# base_pcb_328.net
KiCad netlist of a schematic drawn in EAGLE
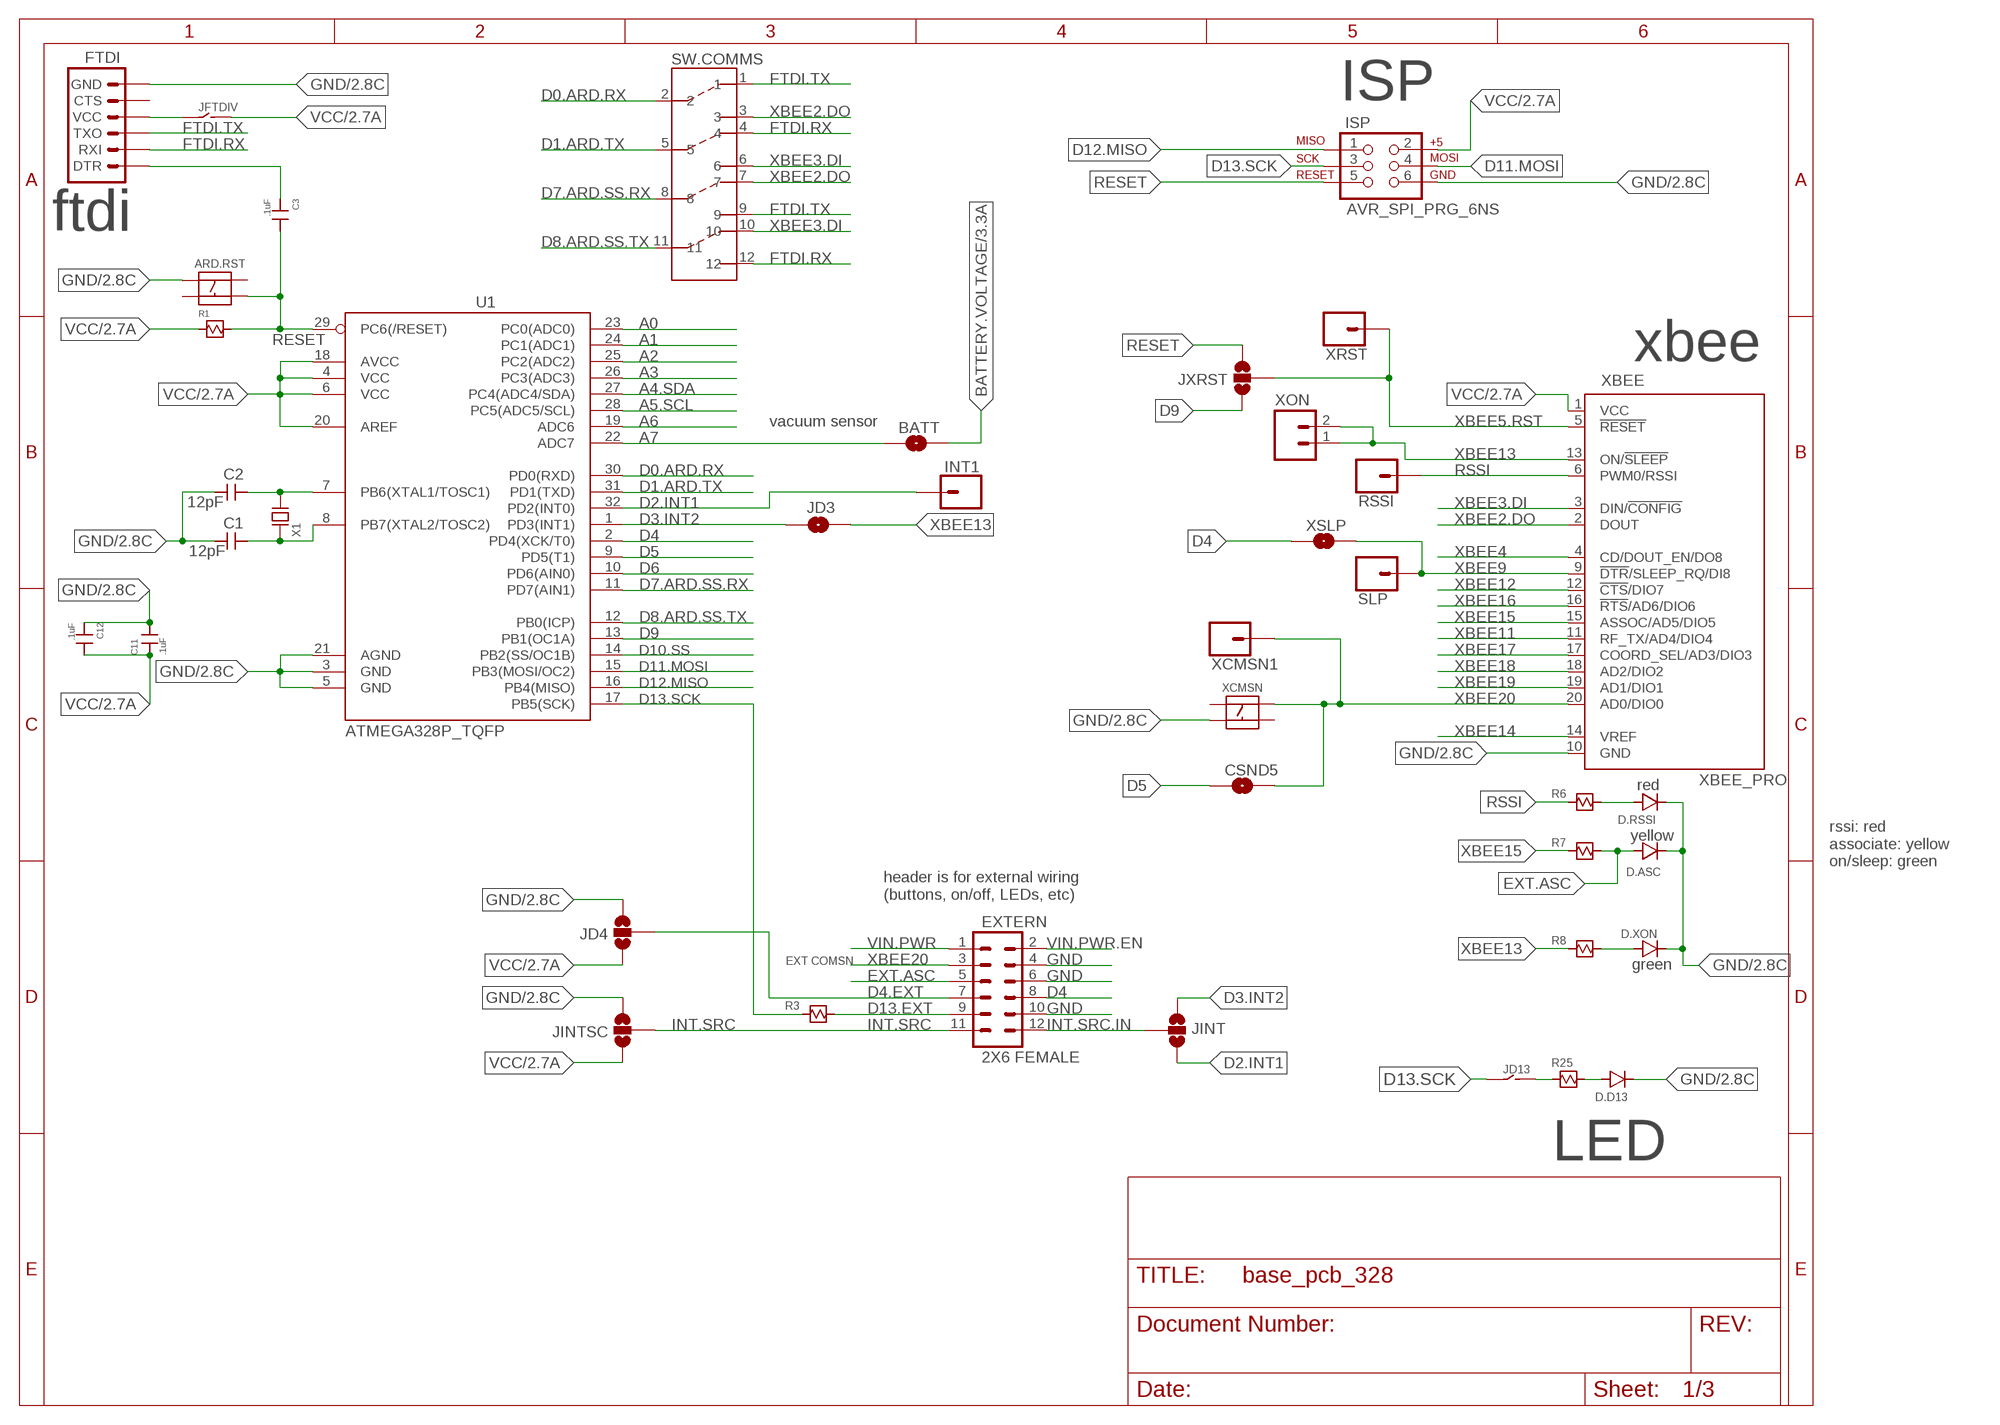
[diagram p0: schematic, sheet 1]
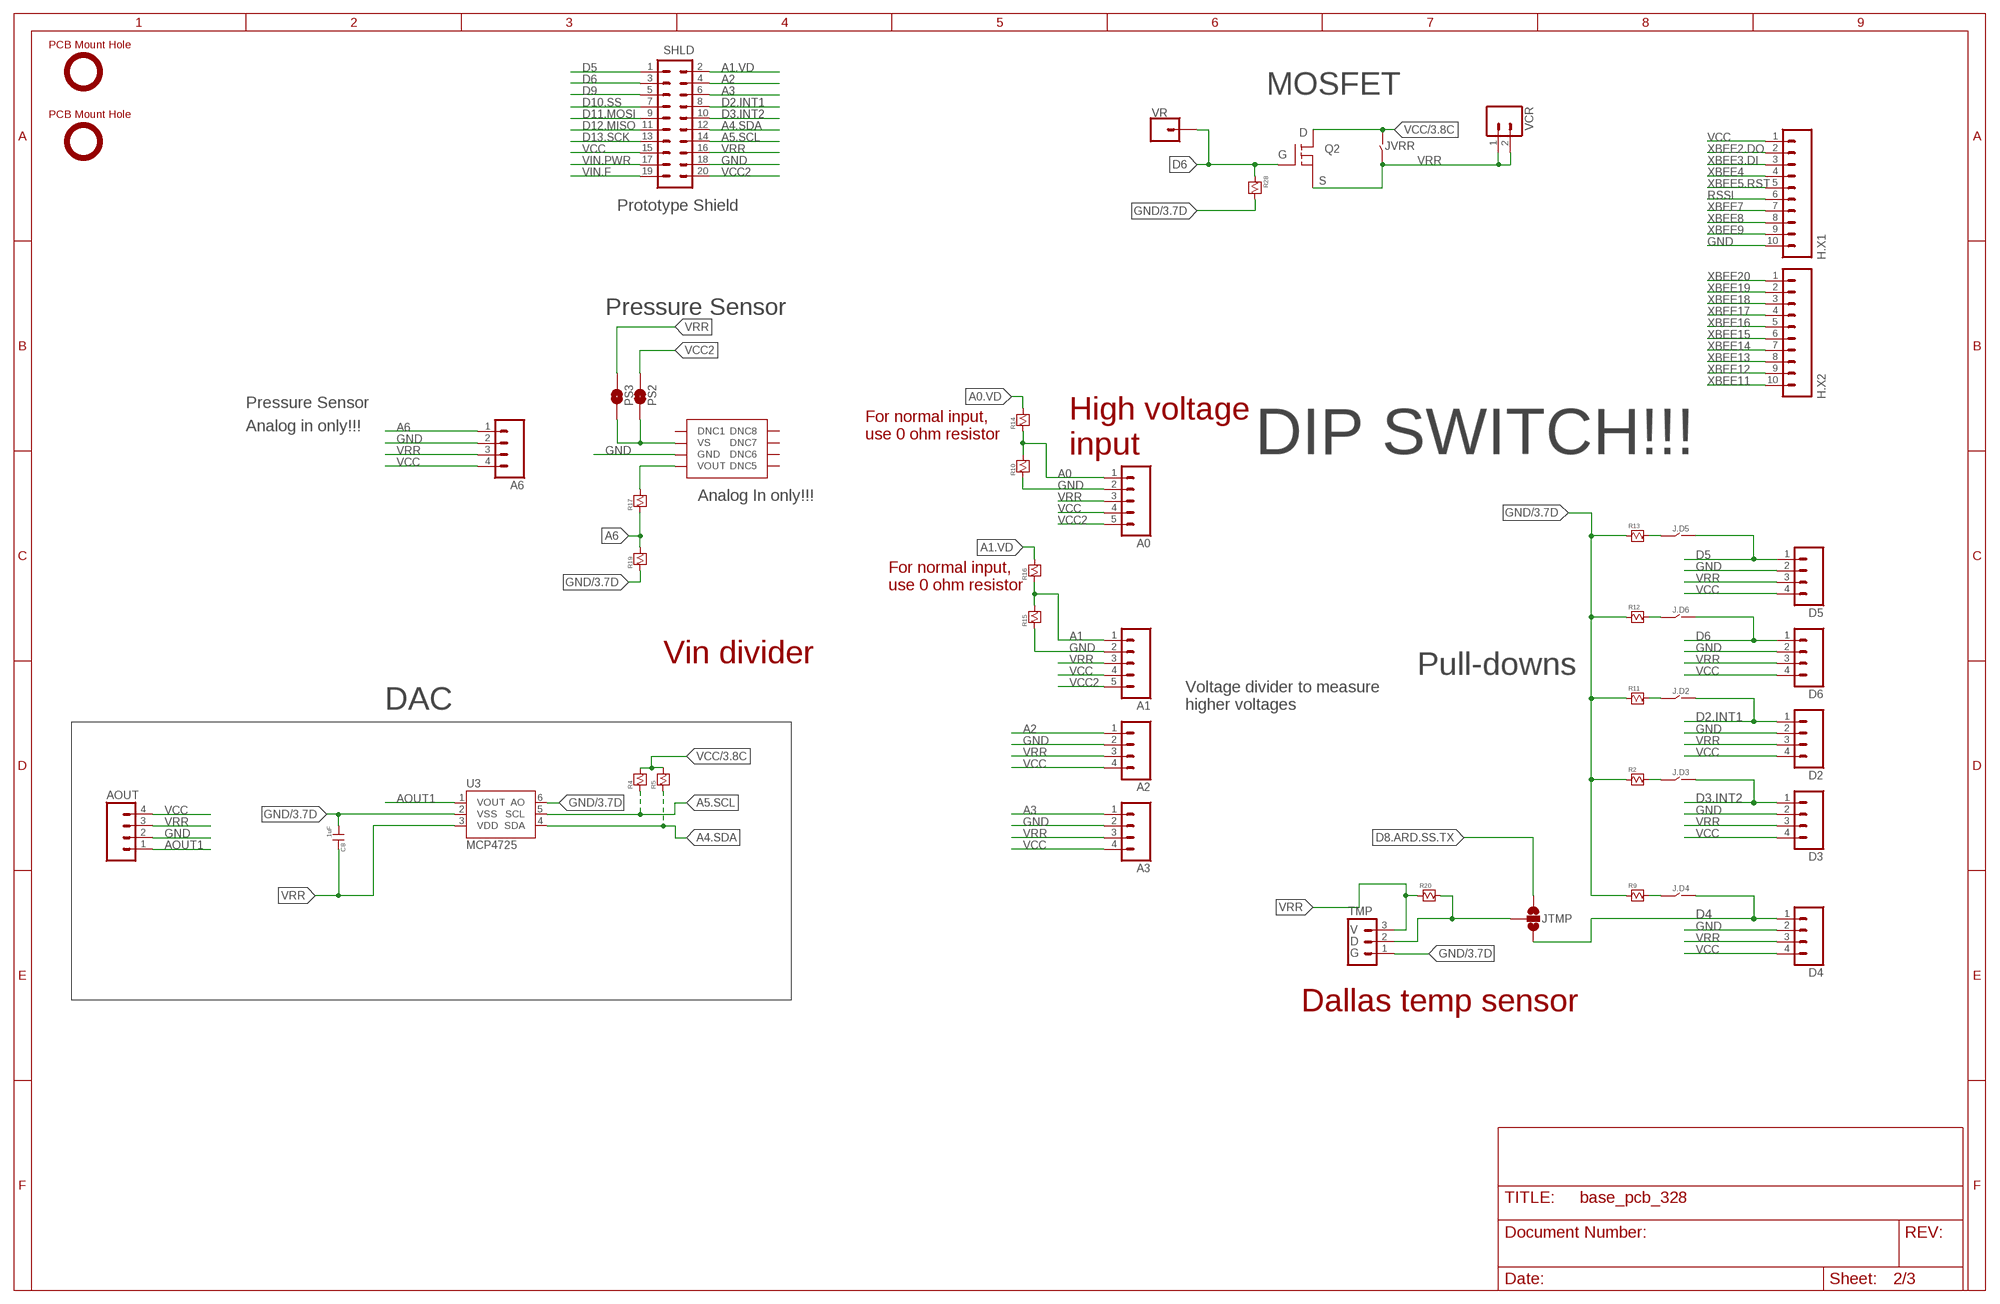
[diagram p1: schematic, sheet 2]
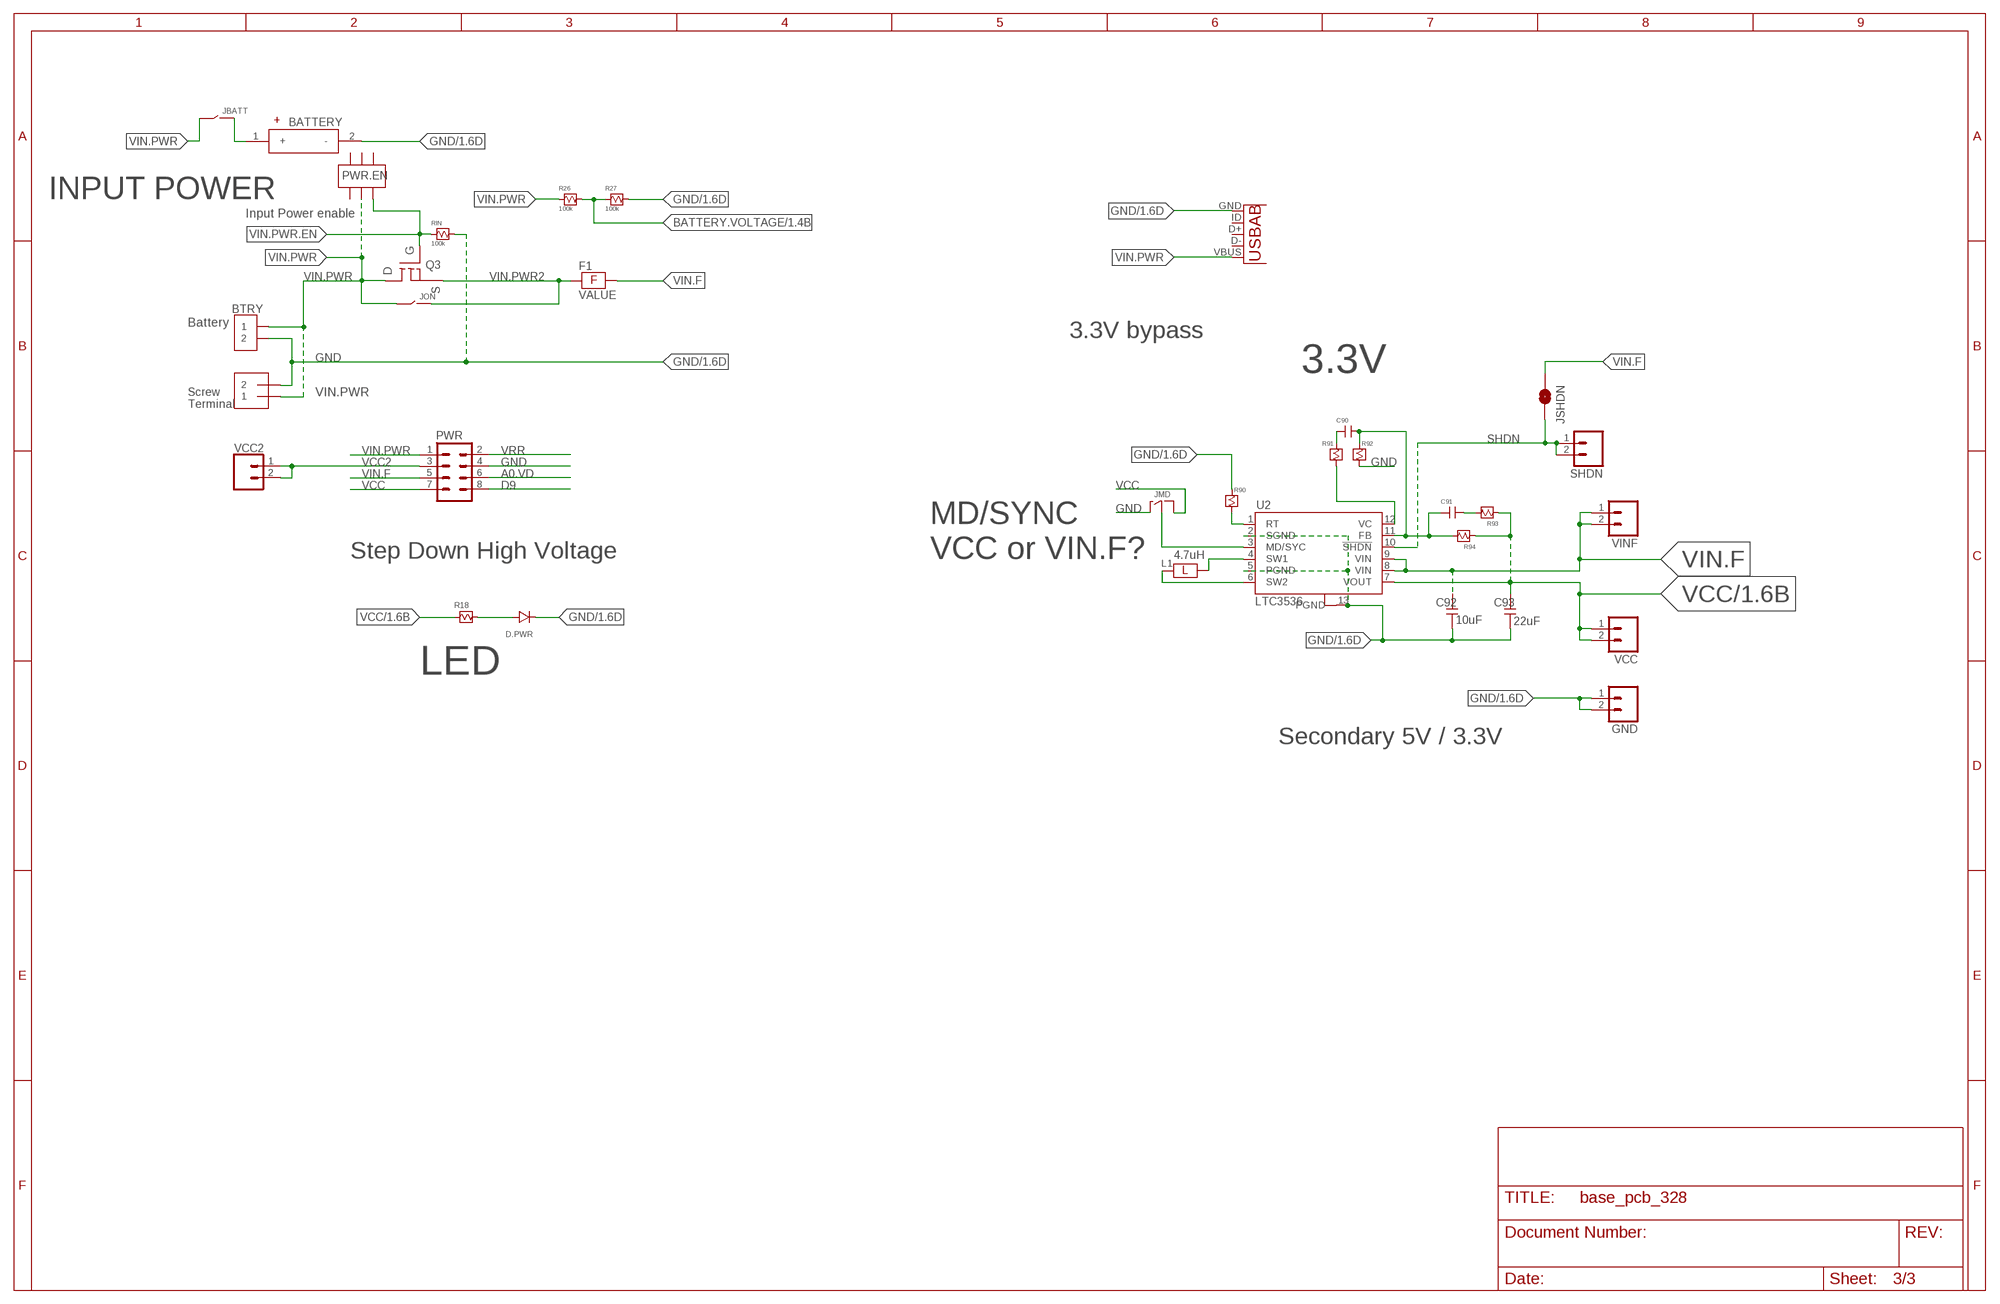
[diagram p2: schematic, sheet 3]

(export (version "E")
  (design (tool "Eeschema 10.0.6"))
  (components
    (comp (ref "ARD.RST")
      (value "C&K_PUSHBUTTON_SMALL_MOM_SPST_SMD")
      (footprint "eagle-import:C&K_PUSHBUTTON_MOM_SMALL_SPST_SMD")
      (libsource (lib "eagle-import") (part "C&K_PUSHBUTTON_SMALL_MOM_SPST_SMD"))
    )
    (comp (ref "BATT")
      (value "JUMPER-PAD-2-NOYES_SILK")
      (footprint "eagle-import:PAD-JUMPER-2-NO_YES_SILK")
      (libsource (lib "eagle-import") (part "JUMPER-PAD-2-NOYES_SILK"))
    )
    (comp (ref "C1")
      (value "12pF")
      (footprint "eagle-import:0603_CAPACITOR")
      (libsource (lib "eagle-import") (part "0603_CAPACITOR"))
    )
    (comp (ref "C2")
      (value "12pF")
      (footprint "eagle-import:0603_CAPACITOR")
      (libsource (lib "eagle-import") (part "0603_CAPACITOR"))
    )
    (comp (ref "C3")
      (value ".1uF")
      (footprint "eagle-import:0603_CAPACITOR")
      (libsource (lib "eagle-import") (part "0603_CAPACITOR"))
    )
    (comp (ref "C11")
      (value ".1uF")
      (footprint "eagle-import:0402_CAPACITOR")
      (libsource (lib "eagle-import") (part "0402_CAPACITOR"))
    )
    (comp (ref "C12")
      (value ".1uF")
      (footprint "eagle-import:0402_CAPACITOR")
      (libsource (lib "eagle-import") (part "0402_CAPACITOR"))
    )
    (comp (ref "CSND5")
      (value "JUMPER-PAD-2-NOYES_SILK")
      (footprint "eagle-import:PAD-JUMPER-2-NO_YES_SILK")
      (libsource (lib "eagle-import") (part "JUMPER-PAD-2-NOYES_SILK"))
    )
    (comp (ref "D.ASC")
      (value "0603_LED")
      (footprint "eagle-import:0603_LED")
      (libsource (lib "eagle-import") (part "0603_LED"))
    )
    (comp (ref "D.D13")
      (value "0603_LED")
      (footprint "eagle-import:0603_LED")
      (libsource (lib "eagle-import") (part "0603_LED"))
    )
    (comp (ref "D.RSSI")
      (value "0603_LED")
      (footprint "eagle-import:0603_LED")
      (libsource (lib "eagle-import") (part "0603_LED"))
    )
    (comp (ref "D.XON")
      (value "0603_LED")
      (footprint "eagle-import:0603_LED")
      (libsource (lib "eagle-import") (part "0603_LED"))
    )
    (comp (ref "EXTERN")
      (value "2X6 FEMALE")
      (footprint "eagle-import:2X6")
      (libsource (lib "eagle-import") (part "M06X2PTH_FEMALE"))
    )
    (comp (ref "FTDI")
      (value "ARDUINO_SERIAL_PROGRAMPTH")
      (footprint "eagle-import:1X06")
      (libsource (lib "eagle-import") (part "ARDUINO_SERIAL_PROGRAMPTH"))
    )
    (comp (ref "INT1")
      (value "M01PTH")
      (footprint "eagle-import:1X01")
      (libsource (lib "eagle-import") (part "M01PTH"))
    )
    (comp (ref "ISP")
      (value "AVR_SPI_PRG_6NS")
      (footprint "eagle-import:2X3-NS")
      (libsource (lib "eagle-import") (part "AVR_SPI_PRG_6NS"))
    )
    (comp (ref "JD3")
      (value "JUMPER-PAD-2-NOYES_SILK")
      (footprint "eagle-import:PAD-JUMPER-2-NO_YES_SILK")
      (libsource (lib "eagle-import") (part "JUMPER-PAD-2-NOYES_SILK"))
    )
    (comp (ref "JD4")
      (value "JUMPER-PAD-3-NOYES_SILK")
      (footprint "eagle-import:PAD-JUMPER-3-NO_YES_SILK")
      (libsource (lib "eagle-import") (part "JUMPER-PAD-3-NOYES_SILK"))
    )
    (comp (ref "JD13")
      (value "JUMPER_2WAY_.1\"_TH")
      (footprint "eagle-import:JUMPER_2WAY_.1__TH")
      (libsource (lib "eagle-import") (part "JUMPER_2WAY_.1{dblquote}_TH"))
    )
    (comp (ref "JFTDIV")
      (value "JUMPER_2WAY_.1\"_TH")
      (footprint "eagle-import:JUMPER_2WAY_.1__TH")
      (libsource (lib "eagle-import") (part "JUMPER_2WAY_.1{dblquote}_TH"))
    )
    (comp (ref "JINT")
      (value "JUMPER-PAD-3-NOYES_SILK")
      (footprint "eagle-import:PAD-JUMPER-3-NO_YES_SILK")
      (libsource (lib "eagle-import") (part "JUMPER-PAD-3-NOYES_SILK"))
    )
    (comp (ref "JINTSC")
      (value "JUMPER-PAD-3-NOYES_SILK")
      (footprint "eagle-import:PAD-JUMPER-3-NO_YES_SILK")
      (libsource (lib "eagle-import") (part "JUMPER-PAD-3-NOYES_SILK"))
    )
    (comp (ref "JXRST")
      (value "JUMPER-PAD-3-NOYES_SILK")
      (footprint "eagle-import:PAD-JUMPER-3-NO_YES_SILK")
      (libsource (lib "eagle-import") (part "JUMPER-PAD-3-NOYES_SILK"))
    )
    (comp (ref "R1")
      (value "0603_RESISTOR")
      (footprint "eagle-import:0603_RESISTOR")
      (libsource (lib "eagle-import") (part "0603_RESISTOR"))
    )
    (comp (ref "R3")
      (value "0603_RESISTOR")
      (footprint "eagle-import:0603_RESISTOR")
      (libsource (lib "eagle-import") (part "0603_RESISTOR"))
    )
    (comp (ref "R6")
      (value "0603_RESISTOR")
      (footprint "eagle-import:0603_RESISTOR")
      (libsource (lib "eagle-import") (part "0603_RESISTOR"))
    )
    (comp (ref "R7")
      (value "0603_RESISTOR")
      (footprint "eagle-import:0603_RESISTOR")
      (libsource (lib "eagle-import") (part "0603_RESISTOR"))
    )
    (comp (ref "R8")
      (value "0603_RESISTOR")
      (footprint "eagle-import:0603_RESISTOR")
      (libsource (lib "eagle-import") (part "0603_RESISTOR"))
    )
    (comp (ref "R25")
      (value "0603_RESISTOR")
      (footprint "eagle-import:0603_RESISTOR")
      (libsource (lib "eagle-import") (part "0603_RESISTOR"))
    )
    (comp (ref "RSSI")
      (value "M01PTH")
      (footprint "eagle-import:1X01")
      (libsource (lib "eagle-import") (part "M01PTH"))
    )
    (comp (ref "SLP")
      (value "M01PTH")
      (footprint "eagle-import:1X01")
      (libsource (lib "eagle-import") (part "M01PTH"))
    )
    (comp (ref "SW.COMMS")
      (value "COPAL_4PDT_SLIDE_SWITCH_TH")
      (footprint "eagle-import:COPAL_4PDT_SLIDE_SWITCH")
      (libsource (lib "eagle-import") (part "COPAL_4PDT_SLIDE_SWITCH_TH"))
    )
    (comp (ref "U1")
      (value "ATMEGA328P_TQFP")
      (footprint "eagle-import:TQFP32-08")
      (libsource (lib "eagle-import") (part "ATMEGA328P_TQFP"))
    )
    (comp (ref "X1")
      (value "ABRACON_ABM3-16.000MHZ-D2Y-T_OSCILLATOR")
      (footprint "eagle-import:ABRACON_ABM3-16.000MHZ-D2Y-T_OSCILLATOR")
      (libsource (lib "eagle-import") (part "ABRACON_ABM3-16.000MHZ-D2Y-T_OSCILLATOR"))
    )
    (comp (ref "XBEE")
      (value "XBEE_PRO")
      (footprint "eagle-import:XBEE_PRO")
      (libsource (lib "eagle-import") (part "XBEE_PRO"))
    )
    (comp (ref "XCMSN")
      (value "C&K_PUSHBUTTON_SMALL_MOM_SPST_SMD")
      (footprint "eagle-import:C&K_PUSHBUTTON_MOM_SMALL_SPST_SMD")
      (libsource (lib "eagle-import") (part "C&K_PUSHBUTTON_SMALL_MOM_SPST_SMD"))
    )
    (comp (ref "XCMSN1")
      (value "M01PTH")
      (footprint "eagle-import:1X01")
      (libsource (lib "eagle-import") (part "M01PTH"))
    )
    (comp (ref "XON")
      (value "M02PTH")
      (footprint "eagle-import:1X02")
      (libsource (lib "eagle-import") (part "M02PTH"))
    )
    (comp (ref "XRST")
      (value "M01PTH")
      (footprint "eagle-import:1X01")
      (libsource (lib "eagle-import") (part "M01PTH"))
    )
    (comp (ref "XSLP")
      (value "JUMPER-PAD-2-NOYES_SILK")
      (footprint "eagle-import:PAD-JUMPER-2-NO_YES_SILK")
      (libsource (lib "eagle-import") (part "JUMPER-PAD-2-NOYES_SILK"))
    )
    (comp (ref "A0")
      (value "M05PTH")
      (footprint "eagle-import:1X05")
      (libsource (lib "eagle-import") (part "M05PTH"))
    )
    (comp (ref "A1")
      (value "M05PTH")
      (footprint "eagle-import:1X05")
      (libsource (lib "eagle-import") (part "M05PTH"))
    )
    (comp (ref "A2")
      (value "M04PTH")
      (footprint "eagle-import:1X04")
      (libsource (lib "eagle-import") (part "M04PTH"))
    )
    (comp (ref "A3")
      (value "M04PTH")
      (footprint "eagle-import:1X04")
      (libsource (lib "eagle-import") (part "M04PTH"))
    )
    (comp (ref "A6")
      (value "M04PTH")
      (footprint "eagle-import:1X04")
      (libsource (lib "eagle-import") (part "M04PTH"))
    )
    (comp (ref "AOUT")
      (value "M04PTH")
      (footprint "eagle-import:1X04")
      (libsource (lib "eagle-import") (part "M04PTH"))
    )
    (comp (ref "C8")
      (value ".1uF")
      (footprint "eagle-import:0603_CAPACITOR")
      (libsource (lib "eagle-import") (part "0603_CAPACITOR"))
    )
    (comp (ref "D2")
      (value "M04PTH")
      (footprint "eagle-import:1X04")
      (libsource (lib "eagle-import") (part "M04PTH"))
    )
    (comp (ref "D3")
      (value "M04PTH")
      (footprint "eagle-import:1X04")
      (libsource (lib "eagle-import") (part "M04PTH"))
    )
    (comp (ref "D4")
      (value "M04PTH")
      (footprint "eagle-import:1X04")
      (libsource (lib "eagle-import") (part "M04PTH"))
    )
    (comp (ref "D5")
      (value "M04PTH")
      (footprint "eagle-import:1X04")
      (libsource (lib "eagle-import") (part "M04PTH"))
    )
    (comp (ref "D6")
      (value "M04PTH")
      (footprint "eagle-import:1X04")
      (libsource (lib "eagle-import") (part "M04PTH"))
    )
    (comp (ref "H.X1")
      (value "M10NO_SILK_PTH_FEMALE")
      (footprint "eagle-import:1X10_NO_SILK")
      (libsource (lib "eagle-import") (part "M10NO_SILK_PTH_FEMALE"))
    )
    (comp (ref "H.X2")
      (value "M10NO_SILK_PTH_FEMALE")
      (footprint "eagle-import:1X10_NO_SILK")
      (libsource (lib "eagle-import") (part "M10NO_SILK_PTH_FEMALE"))
    )
    (comp (ref "J.D2")
      (value "JUMPER_2WAY_.1\"_TH")
      (footprint "eagle-import:JUMPER_2WAY_.1__TH")
      (libsource (lib "eagle-import") (part "JUMPER_2WAY_.1{dblquote}_TH"))
    )
    (comp (ref "J.D3")
      (value "JUMPER_2WAY_.1\"_TH")
      (footprint "eagle-import:JUMPER_2WAY_.1__TH")
      (libsource (lib "eagle-import") (part "JUMPER_2WAY_.1{dblquote}_TH"))
    )
    (comp (ref "J.D4")
      (value "JUMPER_2WAY_.1\"_TH")
      (footprint "eagle-import:JUMPER_2WAY_.1__TH")
      (libsource (lib "eagle-import") (part "JUMPER_2WAY_.1{dblquote}_TH"))
    )
    (comp (ref "J.D5")
      (value "JUMPER_2WAY_.1\"_TH")
      (footprint "eagle-import:JUMPER_2WAY_.1__TH")
      (libsource (lib "eagle-import") (part "JUMPER_2WAY_.1{dblquote}_TH"))
    )
    (comp (ref "J.D6")
      (value "JUMPER_2WAY_.1\"_TH")
      (footprint "eagle-import:JUMPER_2WAY_.1__TH")
      (libsource (lib "eagle-import") (part "JUMPER_2WAY_.1{dblquote}_TH"))
    )
    (comp (ref "JTMP")
      (value "JUMPER-PAD-3-NOYES_SILK")
      (footprint "eagle-import:PAD-JUMPER-3-NO_YES_SILK")
      (libsource (lib "eagle-import") (part "JUMPER-PAD-3-NOYES_SILK"))
    )
    (comp (ref "JVRR")
      (value "JUMPER_2WAY_.1\"_TH")
      (footprint "eagle-import:JUMPER_2WAY_.1__TH")
      (libsource (lib "eagle-import") (part "JUMPER_2WAY_.1{dblquote}_TH"))
    )
    (comp (ref "PS2")
      (value "JUMPER-PAD-2-NOYES_SILK")
      (footprint "eagle-import:PAD-JUMPER-2-NO_YES_SILK")
      (libsource (lib "eagle-import") (part "JUMPER-PAD-2-NOYES_SILK"))
    )
    (comp (ref "PS3")
      (value "JUMPER-PAD-2-NOYES_SILK")
      (footprint "eagle-import:PAD-JUMPER-2-NO_YES_SILK")
      (libsource (lib "eagle-import") (part "JUMPER-PAD-2-NOYES_SILK"))
    )
    (comp (ref "Q2")
      (value "INFINEON_MOSFET_NCH")
      (footprint "eagle-import:INFINEON_MOSFET_NCH_SMD")
      (libsource (lib "eagle-import") (part "INFINEON_MOSFET_NCH"))
    )
    (comp (ref "R2")
      (value "0603_RESISTOR")
      (footprint "eagle-import:0603_RESISTOR")
      (libsource (lib "eagle-import") (part "0603_RESISTOR"))
    )
    (comp (ref "R4")
      (value "0603_RESISTOR")
      (footprint "eagle-import:0603_RESISTOR")
      (libsource (lib "eagle-import") (part "0603_RESISTOR"))
    )
    (comp (ref "R5")
      (value "0603_RESISTOR")
      (footprint "eagle-import:0603_RESISTOR")
      (libsource (lib "eagle-import") (part "0603_RESISTOR"))
    )
    (comp (ref "R9")
      (value "0603_RESISTOR")
      (footprint "eagle-import:0603_RESISTOR")
      (libsource (lib "eagle-import") (part "0603_RESISTOR"))
    )
    (comp (ref "R10")
      (value "0603_RESISTOR")
      (footprint "eagle-import:0603_RESISTOR")
      (libsource (lib "eagle-import") (part "0603_RESISTOR"))
    )
    (comp (ref "R11")
      (value "0603_RESISTOR")
      (footprint "eagle-import:0603_RESISTOR")
      (libsource (lib "eagle-import") (part "0603_RESISTOR"))
    )
    (comp (ref "R12")
      (value "0603_RESISTOR")
      (footprint "eagle-import:0603_RESISTOR")
      (libsource (lib "eagle-import") (part "0603_RESISTOR"))
    )
    (comp (ref "R13")
      (value "0603_RESISTOR")
      (footprint "eagle-import:0603_RESISTOR")
      (libsource (lib "eagle-import") (part "0603_RESISTOR"))
    )
    (comp (ref "R14")
      (value "0603_RESISTOR")
      (footprint "eagle-import:0603_RESISTOR")
      (libsource (lib "eagle-import") (part "0603_RESISTOR"))
    )
    (comp (ref "R15")
      (value "0603_RESISTOR")
      (footprint "eagle-import:0603_RESISTOR")
      (libsource (lib "eagle-import") (part "0603_RESISTOR"))
    )
    (comp (ref "R16")
      (value "0603_RESISTOR")
      (footprint "eagle-import:0603_RESISTOR")
      (libsource (lib "eagle-import") (part "0603_RESISTOR"))
    )
    (comp (ref "R17")
      (value "0603_RESISTOR")
      (footprint "eagle-import:0603_RESISTOR")
      (libsource (lib "eagle-import") (part "0603_RESISTOR"))
    )
    (comp (ref "R19")
      (value "0603_RESISTOR")
      (footprint "eagle-import:0603_RESISTOR")
      (libsource (lib "eagle-import") (part "0603_RESISTOR"))
    )
    (comp (ref "R20")
      (value "0603_RESISTOR")
      (footprint "eagle-import:0603_RESISTOR")
      (libsource (lib "eagle-import") (part "0603_RESISTOR"))
    )
    (comp (ref "R28")
      (value "0603_RESISTOR")
      (footprint "eagle-import:0603_RESISTOR")
      (libsource (lib "eagle-import") (part "0603_RESISTOR"))
    )
    (comp (ref "SHLD")
      (value "M10X2")
      (footprint "eagle-import:2X10")
      (libsource (lib "eagle-import") (part "M10X2"))
    )
    (comp (ref "TMP")
      (value "M03PTH")
      (footprint "eagle-import:1X03")
      (libsource (lib "eagle-import") (part "M03PTH"))
    )
    (comp (ref "U$9")
      (value "MPXV6115VC6U")
      (footprint "eagle-import:MPXV6115VC6U")
      (libsource (lib "eagle-import") (part "MPXV6115VC6U"))
    )
    (comp (ref "U$13")
      (value "PCB_HOLE")
      (footprint "eagle-import:PCB_HOLE")
      (libsource (lib "eagle-import") (part "PCB_HOLE"))
    )
    (comp (ref "U$14")
      (value "PCB_HOLE")
      (footprint "eagle-import:PCB_HOLE")
      (libsource (lib "eagle-import") (part "PCB_HOLE"))
    )
    (comp (ref "U3")
      (value "MCP4725")
      (footprint "eagle-import:SOT23-6")
      (libsource (lib "eagle-import") (part "MCP4725SOT-23"))
    )
    (comp (ref "VCR")
      (value "M02PTH")
      (footprint "eagle-import:1X02")
      (libsource (lib "eagle-import") (part "M02PTH"))
    )
    (comp (ref "VR")
      (value "M01PTH")
      (footprint "eagle-import:1X01")
      (libsource (lib "eagle-import") (part "M01PTH"))
    )
    (comp (ref "5V")
      (value "USB-AB")
      (footprint "eagle-import:USB-AB-MICRO-SMD")
      (libsource (lib "eagle-import") (part "USB-AB"))
    )
    (comp (ref "BATTERY")
      (value "BATTERY_HOLDER_18650")
      (footprint "eagle-import:BATTERY_HOLDER_18650")
      (libsource (lib "eagle-import") (part "BATTERY_HOLDER_18650"))
    )
    (comp (ref "BTRY")
      (value "MOLEX_2PIN_LOCKING_TH")
      (footprint "eagle-import:MOLEX_2PIN_LOCKING_TH")
      (libsource (lib "eagle-import") (part "MOLEX_2PIN_LOCKING_TH"))
    )
    (comp (ref "C90")
      (value "0603_CAPACITOR")
      (footprint "eagle-import:0603_CAPACITOR")
      (libsource (lib "eagle-import") (part "0603_CAPACITOR"))
    )
    (comp (ref "C91")
      (value "0603_CAPACITOR")
      (footprint "eagle-import:0603_CAPACITOR")
      (libsource (lib "eagle-import") (part "0603_CAPACITOR"))
    )
    (comp (ref "C92")
      (value "10uF")
      (footprint "eagle-import:0805_CAPACITOR")
      (libsource (lib "eagle-import") (part "0805_CAPACITOR"))
    )
    (comp (ref "C93")
      (value "22uF")
      (footprint "eagle-import:0805_CAPACITOR")
      (libsource (lib "eagle-import") (part "0805_CAPACITOR"))
    )
    (comp (ref "D.PWR")
      (value "0603_LED")
      (footprint "eagle-import:0603_LED")
      (libsource (lib "eagle-import") (part "0603_LED"))
    )
    (comp (ref "F1")
      (value "PTC_FUSE_PTC_1206")
      (footprint "eagle-import:BEL_FUSE_PTC_FUSE_1206")
      (libsource (lib "eagle-import") (part "PTC_FUSE_PTC_1206"))
    )
    (comp (ref "GND")
      (value "M02PTH")
      (footprint "eagle-import:1X02")
      (libsource (lib "eagle-import") (part "M02PTH"))
    )
    (comp (ref "INPUT.PWR")
      (value "1X2-3.5MM")
      (footprint "eagle-import:1X2-3.5MM")
      (libsource (lib "eagle-import") (part "1X2-3.5MM"))
    )
    (comp (ref "JBATT")
      (value "JUMPER_2WAY_.1\"_TH")
      (footprint "eagle-import:JUMPER_2WAY_.1__TH")
      (libsource (lib "eagle-import") (part "JUMPER_2WAY_.1{dblquote}_TH"))
    )
    (comp (ref "JMD")
      (value "JUMPER_3WAY_.1\"_TH")
      (footprint "eagle-import:JUMPER_3WAY_.1__TH")
      (libsource (lib "eagle-import") (part "JUMPER_3WAY_.1{dblquote}_TH"))
    )
    (comp (ref "JON")
      (value "JUMPER_2WAY_.1\"_TH")
      (footprint "eagle-import:JUMPER_2WAY_.1__TH")
      (libsource (lib "eagle-import") (part "JUMPER_2WAY_.1{dblquote}_TH"))
    )
    (comp (ref "JSHDN")
      (value "JUMPER-PAD-2-NOYES_SILK")
      (footprint "eagle-import:PAD-JUMPER-2-NO_YES_SILK")
      (libsource (lib "eagle-import") (part "JUMPER-PAD-2-NOYES_SILK"))
    )
    (comp (ref "L1")
      (value "4.7uH")
      (footprint "eagle-import:BOURNS_INDUCTOR_SMD")
      (libsource (lib "eagle-import") (part "BOURNS_INDUCTOR_SMD"))
    )
    (comp (ref "PWR")
      (value "M04X2")
      (footprint "eagle-import:2X4")
      (libsource (lib "eagle-import") (part "M04X2"))
    )
    (comp (ref "PWR.EN")
      (value "C&K_DPDT_SLIDE_SWITCH_SMD_HIDDEN_PADS")
      (footprint "eagle-import:C&K_SLIDE_SWITCH_DPDT_SMD_HIDDEN_PADS")
      (libsource (lib "eagle-import") (part "C&K_DPDT_SLIDE_SWITCH_SMD_HIDDEN_PADS"))
    )
    (comp (ref "Q3")
      (value "INFINEON_MOSFET_NCH")
      (footprint "eagle-import:INFINEON_MOSFET_NCH_SMD")
      (libsource (lib "eagle-import") (part "INFINEON_MOSFET_NCH"))
    )
    (comp (ref "R18")
      (value "0603_RESISTOR")
      (footprint "eagle-import:0603_RESISTOR")
      (libsource (lib "eagle-import") (part "0603_RESISTOR"))
    )
    (comp (ref "R26")
      (value "100k")
      (footprint "eagle-import:0603_RESISTOR")
      (libsource (lib "eagle-import") (part "0603_RESISTOR"))
    )
    (comp (ref "R27")
      (value "100k")
      (footprint "eagle-import:0603_RESISTOR")
      (libsource (lib "eagle-import") (part "0603_RESISTOR"))
    )
    (comp (ref "R90")
      (value "0603_RESISTOR")
      (footprint "eagle-import:0603_RESISTOR")
      (libsource (lib "eagle-import") (part "0603_RESISTOR"))
    )
    (comp (ref "R91")
      (value "0603_RESISTOR")
      (footprint "eagle-import:0603_RESISTOR")
      (libsource (lib "eagle-import") (part "0603_RESISTOR"))
    )
    (comp (ref "R92")
      (value "0603_RESISTOR")
      (footprint "eagle-import:0603_RESISTOR")
      (libsource (lib "eagle-import") (part "0603_RESISTOR"))
    )
    (comp (ref "R93")
      (value "0603_RESISTOR")
      (footprint "eagle-import:0603_RESISTOR")
      (libsource (lib "eagle-import") (part "0603_RESISTOR"))
    )
    (comp (ref "R94")
      (value "0603_RESISTOR")
      (footprint "eagle-import:0603_RESISTOR")
      (libsource (lib "eagle-import") (part "0603_RESISTOR"))
    )
    (comp (ref "RIN")
      (value "100k")
      (footprint "eagle-import:0603_RESISTOR")
      (libsource (lib "eagle-import") (part "0603_RESISTOR"))
    )
    (comp (ref "SHDN")
      (value "M02PTH")
      (footprint "eagle-import:1X02")
      (libsource (lib "eagle-import") (part "M02PTH"))
    )
    (comp (ref "U2")
      (value "LTC3536_ADJ_12PIN")
      (footprint "eagle-import:LTC3536_ADJ_12PIN")
      (libsource (lib "eagle-import") (part "LTC3536_ADJ_12PIN"))
    )
    (comp (ref "VCC")
      (value "M02PTH")
      (footprint "eagle-import:1X02")
      (libsource (lib "eagle-import") (part "M02PTH"))
    )
    (comp (ref "VCC2")
      (value "M02PTH")
      (footprint "eagle-import:1X02")
      (libsource (lib "eagle-import") (part "M02PTH"))
    )
    (comp (ref "VINF")
      (value "M02PTH")
      (footprint "eagle-import:1X02")
      (libsource (lib "eagle-import") (part "M02PTH"))
    )
  )
  (nets
    (net (code "1") (name "A0") (class "Default")
      (node (ref "A0") (pin "1") (pinfunction "1_1") (pintype "passive"))
      (node (ref "R10") (pin "2") (pinfunction "2_2") (pintype "bidirectional"))
      (node (ref "R14") (pin "1") (pinfunction "1_1") (pintype "bidirectional"))
      (node (ref "U1") (pin "23") (pinfunction "PC0(ADC0)_23") (pintype "bidirectional"))
    )
    (net (code "2") (name "A0.VD") (class "Default")
      (node (ref "PWR") (pin "6") (pinfunction "6_6") (pintype "passive"))
      (node (ref "R14") (pin "2") (pinfunction "2_2") (pintype "bidirectional"))
    )
    (net (code "3") (name "A1") (class "Default")
      (node (ref "A1") (pin "1") (pinfunction "1_1") (pintype "passive"))
      (node (ref "R15") (pin "2") (pinfunction "2_2") (pintype "bidirectional"))
      (node (ref "R16") (pin "1") (pinfunction "1_1") (pintype "bidirectional"))
      (node (ref "U1") (pin "24") (pinfunction "PC1(ADC1)_24") (pintype "bidirectional"))
    )
    (net (code "4") (name "A1.VD") (class "Default")
      (node (ref "R16") (pin "2") (pinfunction "2_2") (pintype "bidirectional"))
      (node (ref "SHLD") (pin "2") (pinfunction "2_2") (pintype "passive"))
    )
    (net (code "5") (name "A2") (class "Default")
      (node (ref "A2") (pin "1") (pinfunction "1_1") (pintype "passive"))
      (node (ref "SHLD") (pin "4") (pinfunction "4_4") (pintype "passive"))
      (node (ref "U1") (pin "25") (pinfunction "PC2(ADC2)_25") (pintype "bidirectional"))
    )
    (net (code "6") (name "A3") (class "Default")
      (node (ref "A3") (pin "1") (pinfunction "1_1") (pintype "passive"))
      (node (ref "SHLD") (pin "6") (pinfunction "6_6") (pintype "passive"))
      (node (ref "U1") (pin "26") (pinfunction "PC3(ADC3)_26") (pintype "bidirectional"))
    )
    (net (code "7") (name "A4.SDA") (class "Default")
      (node (ref "R5") (pin "1") (pinfunction "1_1") (pintype "bidirectional"))
      (node (ref "SHLD") (pin "12") (pinfunction "12_12") (pintype "passive"))
      (node (ref "U1") (pin "27") (pinfunction "PC4(ADC4/SDA)_27") (pintype "bidirectional"))
      (node (ref "U3") (pin "4") (pinfunction "SDA_4") (pintype "bidirectional"))
    )
    (net (code "8") (name "A5.SCL") (class "Default")
      (node (ref "R4") (pin "1") (pinfunction "1_1") (pintype "bidirectional"))
      (node (ref "SHLD") (pin "14") (pinfunction "14_14") (pintype "passive"))
      (node (ref "U1") (pin "28") (pinfunction "PC5(ADC5/SCL)_28") (pintype "bidirectional"))
      (node (ref "U3") (pin "5") (pinfunction "SCL_5") (pintype "bidirectional"))
    )
    (net (code "9") (name "A6") (class "Default")
      (node (ref "A6") (pin "1") (pinfunction "1_1") (pintype "passive"))
      (node (ref "R17") (pin "1") (pinfunction "1_1") (pintype "bidirectional"))
      (node (ref "R19") (pin "2") (pinfunction "2_2") (pintype "bidirectional"))
      (node (ref "U1") (pin "19") (pinfunction "ADC6_19") (pintype "bidirectional"))
    )
    (net (code "10") (name "A7") (class "Default")
      (node (ref "BATT") (pin "1") (pinfunction "1_1") (pintype "passive"))
      (node (ref "U1") (pin "22") (pinfunction "ADC7_22") (pintype "bidirectional"))
    )
    (net (code "11") (name "AOUT1") (class "Default")
      (node (ref "AOUT") (pin "1") (pinfunction "1_1") (pintype "passive"))
      (node (ref "U3") (pin "1") (pinfunction "VOUT_1") (pintype "bidirectional"))
    )
    (net (code "12") (name "BATTERY.VOLTAGE") (class "Default")
      (node (ref "BATT") (pin "2") (pinfunction "2_2") (pintype "passive"))
      (node (ref "R26") (pin "2") (pinfunction "2_2") (pintype "bidirectional"))
      (node (ref "R27") (pin "1") (pinfunction "1_1") (pintype "bidirectional"))
    )
    (net (code "13") (name "D0.ARD.RX") (class "Default")
      (node (ref "SW.COMMS") (pin "2") (pinfunction "2_2") (pintype "bidirectional"))
      (node (ref "U1") (pin "30") (pinfunction "PD0(RXD)_30") (pintype "bidirectional"))
    )
    (net (code "14") (name "D1.ARD.TX") (class "Default")
      (node (ref "SW.COMMS") (pin "5") (pinfunction "5_5") (pintype "bidirectional"))
      (node (ref "U1") (pin "31") (pinfunction "PD1(TXD)_31") (pintype "bidirectional"))
    )
    (net (code "15") (name "D2.INT1") (class "Default")
      (node (ref "D2") (pin "1") (pinfunction "1_1") (pintype "passive"))
      (node (ref "INT1") (pin "1") (pinfunction "1_1") (pintype "passive"))
      (node (ref "J.D2") (pin "P$2") (pinfunction "P$2_P$2") (pintype "bidirectional"))
      (node (ref "JINT") (pin "3") (pinfunction "3_3") (pintype "passive"))
      (node (ref "SHLD") (pin "8") (pinfunction "8_8") (pintype "passive"))
      (node (ref "U1") (pin "32") (pinfunction "PD2(INT0)_32") (pintype "bidirectional"))
    )
    (net (code "16") (name "D3.INT2") (class "Default")
      (node (ref "D3") (pin "1") (pinfunction "1_1") (pintype "passive"))
      (node (ref "J.D3") (pin "P$2") (pinfunction "P$2_P$2") (pintype "bidirectional"))
      (node (ref "JD3") (pin "1") (pinfunction "1_1") (pintype "passive"))
      (node (ref "JINT") (pin "1") (pinfunction "1_1") (pintype "passive"))
      (node (ref "SHLD") (pin "10") (pinfunction "10_10") (pintype "passive"))
      (node (ref "U1") (pin "1") (pinfunction "PD3(INT1)_1") (pintype "bidirectional"))
    )
    (net (code "17") (name "D4") (class "Default")
      (node (ref "D4") (pin "1") (pinfunction "1_1") (pintype "passive"))
      (node (ref "EXTERN") (pin "8") (pinfunction "8_8") (pintype "passive"))
      (node (ref "J.D4") (pin "P$2") (pinfunction "P$2_P$2") (pintype "bidirectional"))
      (node (ref "JTMP") (pin "3") (pinfunction "3_3") (pintype "passive"))
      (node (ref "U1") (pin "2") (pinfunction "PD4(XCK/T0)_2") (pintype "bidirectional"))
      (node (ref "XSLP") (pin "1") (pinfunction "1_1") (pintype "passive"))
    )
    (net (code "18") (name "D4.EXT") (class "Default")
      (node (ref "EXTERN") (pin "7") (pinfunction "7_7") (pintype "passive"))
      (node (ref "JD4") (pin "2") (pinfunction "2_2") (pintype "passive"))
    )
    (net (code "19") (name "D5") (class "Default")
      (node (ref "CSND5") (pin "1") (pinfunction "1_1") (pintype "passive"))
      (node (ref "D5") (pin "1") (pinfunction "1_1") (pintype "passive"))
      (node (ref "J.D5") (pin "P$2") (pinfunction "P$2_P$2") (pintype "bidirectional"))
      (node (ref "SHLD") (pin "1") (pinfunction "1_1") (pintype "passive"))
      (node (ref "U1") (pin "9") (pinfunction "PD5(T1)_9") (pintype "bidirectional"))
    )
    (net (code "20") (name "D6") (class "Default")
      (node (ref "D6") (pin "1") (pinfunction "1_1") (pintype "passive"))
      (node (ref "J.D6") (pin "P$2") (pinfunction "P$2_P$2") (pintype "bidirectional"))
      (node (ref "Q2") (pin "G") (pinfunction "G_G") (pintype "bidirectional"))
      (node (ref "R28") (pin "1") (pinfunction "1_1") (pintype "bidirectional"))
      (node (ref "SHLD") (pin "3") (pinfunction "3_3") (pintype "passive"))
      (node (ref "U1") (pin "10") (pinfunction "PD6(AIN0)_10") (pintype "bidirectional"))
      (node (ref "VR") (pin "1") (pinfunction "1_1") (pintype "passive"))
    )
    (net (code "21") (name "D7.ARD.SS.RX") (class "Default")
      (node (ref "SW.COMMS") (pin "8") (pinfunction "8_8") (pintype "bidirectional"))
      (node (ref "U1") (pin "11") (pinfunction "PD7(AIN1)_11") (pintype "bidirectional"))
    )
    (net (code "22") (name "D8.ARD.SS.TX") (class "Default")
      (node (ref "JTMP") (pin "1") (pinfunction "1_1") (pintype "passive"))
      (node (ref "SW.COMMS") (pin "11") (pinfunction "11_11") (pintype "bidirectional"))
      (node (ref "U1") (pin "12") (pinfunction "PB0(ICP)_12") (pintype "bidirectional"))
    )
    (net (code "23") (name "D9") (class "Default")
      (node (ref "JXRST") (pin "1") (pinfunction "1_1") (pintype "passive"))
      (node (ref "PWR") (pin "8") (pinfunction "8_8") (pintype "passive"))
      (node (ref "SHLD") (pin "5") (pinfunction "5_5") (pintype "passive"))
      (node (ref "U1") (pin "13") (pinfunction "PB1(OC1A)_13") (pintype "bidirectional"))
    )
    (net (code "24") (name "D10.SS") (class "Default")
      (node (ref "SHLD") (pin "7") (pinfunction "7_7") (pintype "passive"))
      (node (ref "U1") (pin "14") (pinfunction "PB2(SS/OC1B)_14") (pintype "bidirectional"))
    )
    (net (code "25") (name "D11.MOSI") (class "Default")
      (node (ref "ISP") (pin "4") (pinfunction "4_4") (pintype "passive"))
      (node (ref "SHLD") (pin "9") (pinfunction "9_9") (pintype "passive"))
      (node (ref "U1") (pin "15") (pinfunction "PB3(MOSI/OC2)_15") (pintype "bidirectional"))
    )
    (net (code "26") (name "D12.MISO") (class "Default")
      (node (ref "ISP") (pin "1") (pinfunction "1_1") (pintype "passive"))
      (node (ref "SHLD") (pin "11") (pinfunction "11_11") (pintype "passive"))
      (node (ref "U1") (pin "16") (pinfunction "PB4(MISO)_16") (pintype "bidirectional"))
    )
    (net (code "27") (name "D13.EXT") (class "Default")
      (node (ref "EXTERN") (pin "9") (pinfunction "9_9") (pintype "passive"))
      (node (ref "R3") (pin "2") (pinfunction "2_2") (pintype "bidirectional"))
    )
    (net (code "28") (name "D13.SCK") (class "Default")
      (node (ref "ISP") (pin "3") (pinfunction "3_3") (pintype "passive"))
      (node (ref "JD13") (pin "P$1") (pinfunction "P$1_P$1") (pintype "bidirectional"))
      (node (ref "R3") (pin "1") (pinfunction "1_1") (pintype "bidirectional"))
      (node (ref "SHLD") (pin "13") (pinfunction "13_13") (pintype "passive"))
      (node (ref "U1") (pin "17") (pinfunction "PB5(SCK)_17") (pintype "bidirectional"))
    )
    (net (code "29") (name "EXT.ASC") (class "Default")
      (node (ref "D.ASC") (pin "1") (pinfunction "1_1") (pintype "bidirectional"))
      (node (ref "EXTERN") (pin "5") (pinfunction "5_5") (pintype "passive"))
      (node (ref "R7") (pin "2") (pinfunction "2_2") (pintype "bidirectional"))
    )
    (net (code "30") (name "FTDI.RX") (class "Default")
      (node (ref "FTDI") (pin "2") (pinfunction "RXI_2") (pintype "passive"))
      (node (ref "SW.COMMS") (pin "12") (pinfunction "12_12") (pintype "bidirectional"))
      (node (ref "SW.COMMS") (pin "4") (pinfunction "4_4") (pintype "bidirectional"))
    )
    (net (code "31") (name "FTDI.TX") (class "Default")
      (node (ref "FTDI") (pin "3") (pinfunction "TXO_3") (pintype "passive"))
      (node (ref "SW.COMMS") (pin "1") (pinfunction "1_1") (pintype "bidirectional"))
      (node (ref "SW.COMMS") (pin "9") (pinfunction "9_9") (pintype "bidirectional"))
    )
    (net (code "32") (name "GND") (class "Default")
      (node (ref "5V") (pin "GND") (pinfunction "GND_GND") (pintype "bidirectional"))
      (node (ref "A0") (pin "2") (pinfunction "2_2") (pintype "passive"))
      (node (ref "A1") (pin "2") (pinfunction "2_2") (pintype "passive"))
      (node (ref "A2") (pin "2") (pinfunction "2_2") (pintype "passive"))
      (node (ref "A3") (pin "2") (pinfunction "2_2") (pintype "passive"))
      (node (ref "A6") (pin "2") (pinfunction "2_2") (pintype "passive"))
      (node (ref "AOUT") (pin "2") (pinfunction "2_2") (pintype "passive"))
      (node (ref "ARD.RST") (pin "1") (pinfunction "1_1") (pintype "bidirectional"))
      (node (ref "BATTERY") (pin "2") (pinfunction "-_2") (pintype "bidirectional"))
      (node (ref "BTRY") (pin "2") (pinfunction "2_2") (pintype "bidirectional"))
      (node (ref "C1") (pin "2") (pinfunction "2_2") (pintype "bidirectional"))
      (node (ref "C11") (pin "2") (pinfunction "2_2") (pintype "bidirectional"))
      (node (ref "C12") (pin "1") (pinfunction "1_1") (pintype "bidirectional"))
      (node (ref "C2") (pin "2") (pinfunction "2_2") (pintype "bidirectional"))
      (node (ref "C8") (pin "1") (pinfunction "1_1") (pintype "bidirectional"))
      (node (ref "C92") (pin "1") (pinfunction "P$1_1") (pintype "bidirectional"))
      (node (ref "C93") (pin "1") (pinfunction "P$1_1") (pintype "bidirectional"))
      (node (ref "D.ASC") (pin "2") (pinfunction "2_2") (pintype "bidirectional"))
      (node (ref "D.D13") (pin "2") (pinfunction "2_2") (pintype "bidirectional"))
      (node (ref "D.PWR") (pin "2") (pinfunction "2_2") (pintype "bidirectional"))
      (node (ref "D.RSSI") (pin "2") (pinfunction "2_2") (pintype "bidirectional"))
      (node (ref "D.XON") (pin "2") (pinfunction "2_2") (pintype "bidirectional"))
      (node (ref "D2") (pin "2") (pinfunction "2_2") (pintype "passive"))
      (node (ref "D3") (pin "2") (pinfunction "2_2") (pintype "passive"))
      (node (ref "D4") (pin "2") (pinfunction "2_2") (pintype "passive"))
      (node (ref "D5") (pin "2") (pinfunction "2_2") (pintype "passive"))
      (node (ref "D6") (pin "2") (pinfunction "2_2") (pintype "passive"))
      (node (ref "EXTERN") (pin "10") (pinfunction "10_10") (pintype "passive"))
      (node (ref "EXTERN") (pin "4") (pinfunction "4_4") (pintype "passive"))
      (node (ref "EXTERN") (pin "6") (pinfunction "6_6") (pintype "passive"))
      (node (ref "FTDI") (pin "6") (pinfunction "GND_6") (pintype "passive"))
      (node (ref "GND") (pin "1") (pinfunction "1_1") (pintype "passive"))
      (node (ref "GND") (pin "2") (pinfunction "2_2") (pintype "passive"))
      (node (ref "H.X1") (pin "10") (pinfunction "10_10") (pintype "passive"))
      (node (ref "INPUT.PWR") (pin "2") (pinfunction "2_2") (pintype "passive"))
      (node (ref "ISP") (pin "6") (pinfunction "6_6") (pintype "passive"))
      (node (ref "JD4") (pin "3") (pinfunction "3_3") (pintype "passive"))
      (node (ref "JINTSC") (pin "3") (pinfunction "3_3") (pintype "passive"))
      (node (ref "JMD") (pin "P$3") (pinfunction "P$3_P$3") (pintype "bidirectional"))
      (node (ref "PWR") (pin "4") (pinfunction "4_4") (pintype "passive"))
      (node (ref "R10") (pin "1") (pinfunction "1_1") (pintype "bidirectional"))
      (node (ref "R11") (pin "1") (pinfunction "1_1") (pintype "bidirectional"))
      (node (ref "R12") (pin "1") (pinfunction "1_1") (pintype "bidirectional"))
      (node (ref "R13") (pin "1") (pinfunction "1_1") (pintype "bidirectional"))
      (node (ref "R15") (pin "1") (pinfunction "1_1") (pintype "bidirectional"))
      (node (ref "R19") (pin "1") (pinfunction "1_1") (pintype "bidirectional"))
      (node (ref "R2") (pin "1") (pinfunction "1_1") (pintype "bidirectional"))
      (node (ref "R27") (pin "2") (pinfunction "2_2") (pintype "bidirectional"))
      (node (ref "R28") (pin "2") (pinfunction "2_2") (pintype "bidirectional"))
      (node (ref "R9") (pin "1") (pinfunction "1_1") (pintype "bidirectional"))
      (node (ref "R90") (pin "2") (pinfunction "2_2") (pintype "bidirectional"))
      (node (ref "R92") (pin "1") (pinfunction "1_1") (pintype "bidirectional"))
      (node (ref "RIN") (pin "2") (pinfunction "2_2") (pintype "bidirectional"))
      (node (ref "SHLD") (pin "18") (pinfunction "18_18") (pintype "passive"))
      (node (ref "TMP") (pin "1") (pinfunction "1_1") (pintype "passive"))
      (node (ref "U$9") (pin "3") (pinfunction "GND_3") (pintype "bidirectional"))
      (node (ref "U1") (pin "21") (pinfunction "AGND_21") (pintype "bidirectional"))
      (node (ref "U1") (pin "3") (pinfunction "GND_3") (pintype "bidirectional"))
      (node (ref "U1") (pin "5") (pinfunction "GND_5") (pintype "bidirectional"))
      (node (ref "U2") (pin "13") (pinfunction "PGND_13") (pintype "bidirectional"))
      (node (ref "U2") (pin "2") (pinfunction "SGND_2") (pintype "bidirectional"))
      (node (ref "U2") (pin "5") (pinfunction "PGND_5") (pintype "bidirectional"))
      (node (ref "U3") (pin "2") (pinfunction "VSS_2") (pintype "bidirectional"))
      (node (ref "U3") (pin "6") (pinfunction "AO_6") (pintype "bidirectional"))
      (node (ref "XBEE") (pin "10") (pinfunction "GND_10") (pintype "power_in"))
      (node (ref "XCMSN") (pin "3") (pinfunction "3_3") (pintype "bidirectional"))
    )
    (net (code "33") (name "INT.SRC") (class "Default")
      (node (ref "EXTERN") (pin "11") (pinfunction "11_11") (pintype "passive"))
      (node (ref "JINTSC") (pin "2") (pinfunction "2_2") (pintype "passive"))
    )
    (net (code "34") (name "INT.SRC.IN") (class "Default")
      (node (ref "EXTERN") (pin "12") (pinfunction "12_12") (pintype "passive"))
      (node (ref "JINT") (pin "2") (pinfunction "2_2") (pintype "passive"))
    )
    (net (code "35") (name "Net-(BATTERY-+)") (class "Default")
      (node (ref "BATTERY") (pin "1") (pinfunction "+_1") (pintype "bidirectional"))
      (node (ref "JBATT") (pin "P$2") (pinfunction "P$2_P$2") (pintype "bidirectional"))
    )
    (net (code "36") (name "Net-(C90-Pad1)") (class "Default")
      (node (ref "C90") (pin "1") (pinfunction "1_1") (pintype "bidirectional"))
      (node (ref "R91") (pin "2") (pinfunction "2_2") (pintype "bidirectional"))
    )
    (net (code "37") (name "Net-(C91-Pad2)") (class "Default")
      (node (ref "C91") (pin "2") (pinfunction "2_2") (pintype "bidirectional"))
      (node (ref "R93") (pin "2") (pinfunction "2_2") (pintype "bidirectional"))
    )
    (net (code "38") (name "Net-(D.D13-Pad1)") (class "Default")
      (node (ref "D.D13") (pin "1") (pinfunction "1_1") (pintype "bidirectional"))
      (node (ref "R25") (pin "2") (pinfunction "2_2") (pintype "bidirectional"))
    )
    (net (code "39") (name "Net-(D.PWR-Pad1)") (class "Default")
      (node (ref "D.PWR") (pin "1") (pinfunction "1_1") (pintype "bidirectional"))
      (node (ref "R18") (pin "2") (pinfunction "2_2") (pintype "bidirectional"))
    )
    (net (code "40") (name "Net-(D.RSSI-Pad1)") (class "Default")
      (node (ref "D.RSSI") (pin "1") (pinfunction "1_1") (pintype "bidirectional"))
      (node (ref "R6") (pin "2") (pinfunction "2_2") (pintype "bidirectional"))
    )
    (net (code "41") (name "Net-(D.XON-Pad1)") (class "Default")
      (node (ref "D.XON") (pin "1") (pinfunction "1_1") (pintype "bidirectional"))
      (node (ref "R8") (pin "2") (pinfunction "2_2") (pintype "bidirectional"))
    )
    (net (code "42") (name "Net-(FTDI-DTR)") (class "Default")
      (node (ref "C3") (pin "1") (pinfunction "1_1") (pintype "bidirectional"))
      (node (ref "FTDI") (pin "1") (pinfunction "DTR_1") (pintype "passive"))
    )
    (net (code "43") (name "Net-(FTDI-VCC)") (class "Default")
      (node (ref "FTDI") (pin "4") (pinfunction "VCC_4") (pintype "passive"))
      (node (ref "JFTDIV") (pin "P$1") (pinfunction "P$1_P$1") (pintype "bidirectional"))
    )
    (net (code "44") (name "Net-(J.D2-PadP$1)") (class "Default")
      (node (ref "J.D2") (pin "P$1") (pinfunction "P$1_P$1") (pintype "bidirectional"))
      (node (ref "R11") (pin "2") (pinfunction "2_2") (pintype "bidirectional"))
    )
    (net (code "45") (name "Net-(J.D3-PadP$1)") (class "Default")
      (node (ref "J.D3") (pin "P$1") (pinfunction "P$1_P$1") (pintype "bidirectional"))
      (node (ref "R2") (pin "2") (pinfunction "2_2") (pintype "bidirectional"))
    )
    (net (code "46") (name "Net-(J.D4-PadP$1)") (class "Default")
      (node (ref "J.D4") (pin "P$1") (pinfunction "P$1_P$1") (pintype "bidirectional"))
      (node (ref "R9") (pin "2") (pinfunction "2_2") (pintype "bidirectional"))
    )
    (net (code "47") (name "Net-(J.D5-PadP$1)") (class "Default")
      (node (ref "J.D5") (pin "P$1") (pinfunction "P$1_P$1") (pintype "bidirectional"))
      (node (ref "R13") (pin "2") (pinfunction "2_2") (pintype "bidirectional"))
    )
    (net (code "48") (name "Net-(J.D6-PadP$1)") (class "Default")
      (node (ref "J.D6") (pin "P$1") (pinfunction "P$1_P$1") (pintype "bidirectional"))
      (node (ref "R12") (pin "2") (pinfunction "2_2") (pintype "bidirectional"))
    )
    (net (code "49") (name "Net-(JD13-PadP$2)") (class "Default")
      (node (ref "JD13") (pin "P$2") (pinfunction "P$2_P$2") (pintype "bidirectional"))
      (node (ref "R25") (pin "1") (pinfunction "1_1") (pintype "bidirectional"))
    )
    (net (code "50") (name "Net-(JTMP-Pad2)") (class "Default")
      (node (ref "JTMP") (pin "2") (pinfunction "2_2") (pintype "passive"))
      (node (ref "R20") (pin "2") (pinfunction "2_2") (pintype "bidirectional"))
      (node (ref "TMP") (pin "2") (pinfunction "2_2") (pintype "passive"))
    )
    (net (code "51") (name "Net-(U$9-VOUT)") (class "Default")
      (node (ref "R17") (pin "2") (pinfunction "2_2") (pintype "bidirectional"))
      (node (ref "U$9") (pin "4") (pinfunction "VOUT_4") (pintype "bidirectional"))
    )
    (net (code "52") (name "Net-(U$9-VS)") (class "Default")
      (node (ref "PS2") (pin "1") (pinfunction "1_1") (pintype "passive"))
      (node (ref "PS3") (pin "1") (pinfunction "1_1") (pintype "passive"))
      (node (ref "U$9") (pin "2") (pinfunction "VS_2") (pintype "bidirectional"))
    )
    (net (code "53") (name "Net-(U1-PB6(XTAL1{slash}TOSC1))") (class "Default")
      (node (ref "C2") (pin "1") (pinfunction "1_1") (pintype "bidirectional"))
      (node (ref "U1") (pin "7") (pinfunction "PB6(XTAL1/TOSC1)_7") (pintype "bidirectional"))
      (node (ref "X1") (pin "P$2") (pinfunction "2_P$2") (pintype "bidirectional"))
    )
    (net (code "54") (name "Net-(U1-PB7(XTAL2{slash}TOSC2))") (class "Default")
      (node (ref "C1") (pin "1") (pinfunction "1_1") (pintype "bidirectional"))
      (node (ref "U1") (pin "8") (pinfunction "PB7(XTAL2/TOSC2)_8") (pintype "bidirectional"))
      (node (ref "X1") (pin "P$1") (pinfunction "1_P$1") (pintype "bidirectional"))
    )
    (net (code "55") (name "Net-(U2-FB)") (class "Default")
      (node (ref "C90") (pin "2") (pinfunction "2_2") (pintype "bidirectional"))
      (node (ref "C91") (pin "1") (pinfunction "1_1") (pintype "bidirectional"))
      (node (ref "R92") (pin "2") (pinfunction "2_2") (pintype "bidirectional"))
      (node (ref "R94") (pin "2") (pinfunction "2_2") (pintype "bidirectional"))
      (node (ref "U2") (pin "11") (pinfunction "FB_11") (pintype "bidirectional"))
    )
    (net (code "56") (name "Net-(U2-MD{slash}SYC)") (class "Default")
      (node (ref "JMD") (pin "P$2") (pinfunction "P$2_P$2") (pintype "bidirectional"))
      (node (ref "U2") (pin "3") (pinfunction "MD/SYC_3") (pintype "bidirectional"))
    )
    (net (code "57") (name "Net-(U2-RT)") (class "Default")
      (node (ref "R90") (pin "1") (pinfunction "1_1") (pintype "bidirectional"))
      (node (ref "U2") (pin "1") (pinfunction "RT_1") (pintype "bidirectional"))
    )
    (net (code "58") (name "Net-(U2-SW1)") (class "Default")
      (node (ref "L1") (pin "P$2") (pinfunction "P$2_P$2") (pintype "bidirectional"))
      (node (ref "U2") (pin "4") (pinfunction "SW1_4") (pintype "bidirectional"))
    )
    (net (code "59") (name "Net-(U2-SW2)") (class "Default")
      (node (ref "L1") (pin "P$1") (pinfunction "P$1_P$1") (pintype "bidirectional"))
      (node (ref "U2") (pin "6") (pinfunction "SW2_6") (pintype "bidirectional"))
    )
    (net (code "60") (name "Net-(U2-VC)") (class "Default")
      (node (ref "R91") (pin "1") (pinfunction "1_1") (pintype "bidirectional"))
      (node (ref "U2") (pin "12") (pinfunction "VC_12") (pintype "bidirectional"))
    )
    (net (code "61") (name "RESET") (class "Default")
      (node (ref "ARD.RST") (pin "4") (pinfunction "4_4") (pintype "bidirectional"))
      (node (ref "C3") (pin "2") (pinfunction "2_2") (pintype "bidirectional"))
      (node (ref "ISP") (pin "5") (pinfunction "5_5") (pintype "passive"))
      (node (ref "JXRST") (pin "3") (pinfunction "3_3") (pintype "passive"))
      (node (ref "R1") (pin "2") (pinfunction "2_2") (pintype "bidirectional"))
      (node (ref "U1") (pin "29") (pinfunction "PC6(/RESET)_29") (pintype "bidirectional"))
    )
    (net (code "62") (name "RSSI") (class "Default")
      (node (ref "H.X1") (pin "6") (pinfunction "6_6") (pintype "passive"))
      (node (ref "R6") (pin "1") (pinfunction "1_1") (pintype "bidirectional"))
      (node (ref "RSSI") (pin "1") (pinfunction "1_1") (pintype "passive"))
      (node (ref "XBEE") (pin "6") (pinfunction "PWM0/RSSI_6") (pintype "output"))
    )
    (net (code "63") (name "SHDN") (class "Default")
      (node (ref "JSHDN") (pin "2") (pinfunction "2_2") (pintype "passive"))
      (node (ref "SHDN") (pin "1") (pinfunction "1_1") (pintype "passive"))
      (node (ref "SHDN") (pin "2") (pinfunction "2_2") (pintype "passive"))
      (node (ref "U2") (pin "10") (pinfunction "~{SHDN}_10") (pintype "bidirectional"))
    )
    (net (code "64") (name "VCC") (class "Default")
      (node (ref "A0") (pin "4") (pinfunction "4_4") (pintype "passive"))
      (node (ref "A1") (pin "4") (pinfunction "4_4") (pintype "passive"))
      (node (ref "A2") (pin "4") (pinfunction "4_4") (pintype "passive"))
      (node (ref "A3") (pin "4") (pinfunction "4_4") (pintype "passive"))
      (node (ref "A6") (pin "4") (pinfunction "4_4") (pintype "passive"))
      (node (ref "AOUT") (pin "4") (pinfunction "4_4") (pintype "passive"))
      (node (ref "C11") (pin "1") (pinfunction "1_1") (pintype "bidirectional"))
      (node (ref "C12") (pin "2") (pinfunction "2_2") (pintype "bidirectional"))
      (node (ref "C93") (pin "2") (pinfunction "P$2_2") (pintype "bidirectional"))
      (node (ref "D2") (pin "4") (pinfunction "4_4") (pintype "passive"))
      (node (ref "D3") (pin "4") (pinfunction "4_4") (pintype "passive"))
      (node (ref "D4") (pin "4") (pinfunction "4_4") (pintype "passive"))
      (node (ref "D5") (pin "4") (pinfunction "4_4") (pintype "passive"))
      (node (ref "D6") (pin "4") (pinfunction "4_4") (pintype "passive"))
      (node (ref "H.X1") (pin "1") (pinfunction "1_1") (pintype "passive"))
      (node (ref "ISP") (pin "2") (pinfunction "2_2") (pintype "passive"))
      (node (ref "JD4") (pin "1") (pinfunction "1_1") (pintype "passive"))
      (node (ref "JFTDIV") (pin "P$2") (pinfunction "P$2_P$2") (pintype "bidirectional"))
      (node (ref "JINTSC") (pin "1") (pinfunction "1_1") (pintype "passive"))
      (node (ref "JMD") (pin "P$1") (pinfunction "P$1_P$1") (pintype "bidirectional"))
      (node (ref "JVRR") (pin "P$2") (pinfunction "P$2_P$2") (pintype "bidirectional"))
      (node (ref "PWR") (pin "7") (pinfunction "7_7") (pintype "passive"))
      (node (ref "Q2") (pin "D") (pinfunction "D_D") (pintype "bidirectional"))
      (node (ref "R1") (pin "1") (pinfunction "1_1") (pintype "bidirectional"))
      (node (ref "R18") (pin "1") (pinfunction "1_1") (pintype "bidirectional"))
      (node (ref "R4") (pin "2") (pinfunction "2_2") (pintype "bidirectional"))
      (node (ref "R5") (pin "2") (pinfunction "2_2") (pintype "bidirectional"))
      (node (ref "R93") (pin "1") (pinfunction "1_1") (pintype "bidirectional"))
      (node (ref "R94") (pin "1") (pinfunction "1_1") (pintype "bidirectional"))
      (node (ref "SHLD") (pin "15") (pinfunction "15_15") (pintype "passive"))
      (node (ref "U1") (pin "18") (pinfunction "AVCC_18") (pintype "bidirectional"))
      (node (ref "U1") (pin "20") (pinfunction "AREF_20") (pintype "bidirectional"))
      (node (ref "U1") (pin "4") (pinfunction "VCC_4") (pintype "bidirectional"))
      (node (ref "U1") (pin "6") (pinfunction "VCC_6") (pintype "bidirectional"))
      (node (ref "U2") (pin "7") (pinfunction "VOUT_7") (pintype "bidirectional"))
      (node (ref "VCC") (pin "1") (pinfunction "1_1") (pintype "passive"))
      (node (ref "VCC") (pin "2") (pinfunction "2_2") (pintype "passive"))
      (node (ref "XBEE") (pin "1") (pinfunction "VCC_1") (pintype "power_in"))
    )
    (net (code "65") (name "VCC2") (class "Default")
      (node (ref "A0") (pin "5") (pinfunction "5_5") (pintype "passive"))
      (node (ref "A1") (pin "5") (pinfunction "5_5") (pintype "passive"))
      (node (ref "PS2") (pin "2") (pinfunction "2_2") (pintype "passive"))
      (node (ref "PWR") (pin "3") (pinfunction "3_3") (pintype "passive"))
      (node (ref "SHLD") (pin "20") (pinfunction "20_20") (pintype "passive"))
      (node (ref "VCC2") (pin "1") (pinfunction "1_1") (pintype "passive"))
      (node (ref "VCC2") (pin "2") (pinfunction "2_2") (pintype "passive"))
    )
    (net (code "66") (name "VIN.F") (class "Default")
      (node (ref "C92") (pin "2") (pinfunction "P$2_2") (pintype "bidirectional"))
      (node (ref "F1") (pin "P$2") (pinfunction "P$2_P$2") (pintype "bidirectional"))
      (node (ref "JSHDN") (pin "1") (pinfunction "1_1") (pintype "passive"))
      (node (ref "PWR") (pin "5") (pinfunction "5_5") (pintype "passive"))
      (node (ref "SHLD") (pin "19") (pinfunction "19_19") (pintype "passive"))
      (node (ref "U2") (pin "8") (pinfunction "VIN_8") (pintype "bidirectional"))
      (node (ref "U2") (pin "9") (pinfunction "VIN_9") (pintype "bidirectional"))
      (node (ref "VINF") (pin "1") (pinfunction "1_1") (pintype "passive"))
      (node (ref "VINF") (pin "2") (pinfunction "2_2") (pintype "passive"))
    )
    (net (code "67") (name "VIN.PWR") (class "Default")
      (node (ref "5V") (pin "VBUS") (pinfunction "VBUS_VBUS") (pintype "bidirectional"))
      (node (ref "BTRY") (pin "1") (pinfunction "1_1") (pintype "bidirectional"))
      (node (ref "EXTERN") (pin "1") (pinfunction "1_1") (pintype "passive"))
      (node (ref "INPUT.PWR") (pin "1") (pinfunction "1_1") (pintype "passive"))
      (node (ref "JBATT") (pin "P$1") (pinfunction "P$1_P$1") (pintype "bidirectional"))
      (node (ref "JON") (pin "P$1") (pinfunction "P$1_P$1") (pintype "bidirectional"))
      (node (ref "PWR") (pin "1") (pinfunction "1_1") (pintype "passive"))
      (node (ref "PWR.EN") (pin "5") (pinfunction "5_5") (pintype "bidirectional"))
      (node (ref "Q3") (pin "D") (pinfunction "D_D") (pintype "bidirectional"))
      (node (ref "R26") (pin "1") (pinfunction "1_1") (pintype "bidirectional"))
      (node (ref "SHLD") (pin "17") (pinfunction "17_17") (pintype "passive"))
    )
    (net (code "68") (name "VIN.PWR.EN") (class "Default")
      (node (ref "EXTERN") (pin "2") (pinfunction "2_2") (pintype "passive"))
      (node (ref "PWR.EN") (pin "4") (pinfunction "4_4") (pintype "bidirectional"))
      (node (ref "Q3") (pin "G") (pinfunction "G_G") (pintype "bidirectional"))
      (node (ref "RIN") (pin "1") (pinfunction "1_1") (pintype "bidirectional"))
    )
    (net (code "69") (name "VIN.PWR2") (class "Default")
      (node (ref "F1") (pin "P$1") (pinfunction "P$1_P$1") (pintype "bidirectional"))
      (node (ref "JON") (pin "P$2") (pinfunction "P$2_P$2") (pintype "bidirectional"))
      (node (ref "Q3") (pin "S") (pinfunction "S_S") (pintype "bidirectional"))
    )
    (net (code "70") (name "VRR") (class "Default")
      (node (ref "A0") (pin "3") (pinfunction "3_3") (pintype "passive"))
      (node (ref "A1") (pin "3") (pinfunction "3_3") (pintype "passive"))
      (node (ref "A2") (pin "3") (pinfunction "3_3") (pintype "passive"))
      (node (ref "A3") (pin "3") (pinfunction "3_3") (pintype "passive"))
      (node (ref "A6") (pin "3") (pinfunction "3_3") (pintype "passive"))
      (node (ref "AOUT") (pin "3") (pinfunction "3_3") (pintype "passive"))
      (node (ref "C8") (pin "2") (pinfunction "2_2") (pintype "bidirectional"))
      (node (ref "D2") (pin "3") (pinfunction "3_3") (pintype "passive"))
      (node (ref "D3") (pin "3") (pinfunction "3_3") (pintype "passive"))
      (node (ref "D4") (pin "3") (pinfunction "3_3") (pintype "passive"))
      (node (ref "D5") (pin "3") (pinfunction "3_3") (pintype "passive"))
      (node (ref "D6") (pin "3") (pinfunction "3_3") (pintype "passive"))
      (node (ref "JVRR") (pin "P$1") (pinfunction "P$1_P$1") (pintype "bidirectional"))
      (node (ref "PS3") (pin "2") (pinfunction "2_2") (pintype "passive"))
      (node (ref "PWR") (pin "2") (pinfunction "2_2") (pintype "passive"))
      (node (ref "Q2") (pin "S") (pinfunction "S_S") (pintype "bidirectional"))
      (node (ref "R20") (pin "1") (pinfunction "1_1") (pintype "bidirectional"))
      (node (ref "SHLD") (pin "16") (pinfunction "16_16") (pintype "passive"))
      (node (ref "TMP") (pin "3") (pinfunction "3_3") (pintype "passive"))
      (node (ref "U3") (pin "3") (pinfunction "VDD_3") (pintype "bidirectional"))
      (node (ref "VCR") (pin "1") (pinfunction "1_1") (pintype "passive"))
      (node (ref "VCR") (pin "2") (pinfunction "2_2") (pintype "passive"))
    )
    (net (code "71") (name "XBEE2.DO") (class "Default")
      (node (ref "H.X1") (pin "2") (pinfunction "2_2") (pintype "passive"))
      (node (ref "SW.COMMS") (pin "3") (pinfunction "3_3") (pintype "bidirectional"))
      (node (ref "SW.COMMS") (pin "7") (pinfunction "7_7") (pintype "bidirectional"))
      (node (ref "XBEE") (pin "2") (pinfunction "DOUT_2") (pintype "output"))
    )
    (net (code "72") (name "XBEE3.DI") (class "Default")
      (node (ref "H.X1") (pin "3") (pinfunction "3_3") (pintype "passive"))
      (node (ref "SW.COMMS") (pin "10") (pinfunction "10_10") (pintype "bidirectional"))
      (node (ref "SW.COMMS") (pin "6") (pinfunction "6_6") (pintype "bidirectional"))
      (node (ref "XBEE") (pin "3") (pinfunction "DIN/~{CONFIG}_3") (pintype "input"))
    )
    (net (code "73") (name "XBEE4") (class "Default")
      (node (ref "H.X1") (pin "4") (pinfunction "4_4") (pintype "passive"))
      (node (ref "XBEE") (pin "4") (pinfunction "CD/DOUT_EN/DO8_4") (pintype "output"))
    )
    (net (code "74") (name "XBEE5.RST") (class "Default")
      (node (ref "H.X1") (pin "5") (pinfunction "5_5") (pintype "passive"))
      (node (ref "JXRST") (pin "2") (pinfunction "2_2") (pintype "passive"))
      (node (ref "XBEE") (pin "5") (pinfunction "~{RESET}_5") (pintype "input"))
      (node (ref "XRST") (pin "1") (pinfunction "1_1") (pintype "passive"))
    )
    (net (code "75") (name "XBEE7") (class "Default")
      (node (ref "H.X1") (pin "7") (pinfunction "7_7") (pintype "passive"))
    )
    (net (code "76") (name "XBEE8") (class "Default")
      (node (ref "H.X1") (pin "8") (pinfunction "8_8") (pintype "passive"))
    )
    (net (code "77") (name "XBEE9") (class "Default")
      (node (ref "H.X1") (pin "9") (pinfunction "9_9") (pintype "passive"))
      (node (ref "SLP") (pin "1") (pinfunction "1_1") (pintype "passive"))
      (node (ref "XBEE") (pin "9") (pinfunction "~{DTR}/SLEEP_RQ/DI8_9") (pintype "bidirectional"))
      (node (ref "XSLP") (pin "2") (pinfunction "2_2") (pintype "passive"))
    )
    (net (code "78") (name "XBEE11") (class "Default")
      (node (ref "H.X2") (pin "10") (pinfunction "10_10") (pintype "passive"))
      (node (ref "XBEE") (pin "11") (pinfunction "RF_TX/AD4/DIO4_11") (pintype "bidirectional"))
    )
    (net (code "79") (name "XBEE12") (class "Default")
      (node (ref "H.X2") (pin "9") (pinfunction "9_9") (pintype "passive"))
      (node (ref "XBEE") (pin "12") (pinfunction "~{CTS}/DIO7_12") (pintype "bidirectional"))
    )
    (net (code "80") (name "XBEE13") (class "Default")
      (node (ref "H.X2") (pin "8") (pinfunction "8_8") (pintype "passive"))
      (node (ref "JD3") (pin "2") (pinfunction "2_2") (pintype "passive"))
      (node (ref "R8") (pin "1") (pinfunction "1_1") (pintype "bidirectional"))
      (node (ref "XBEE") (pin "13") (pinfunction "ON/~{SLEEP}_13") (pintype "output"))
      (node (ref "XON") (pin "1") (pinfunction "1_1") (pintype "passive"))
      (node (ref "XON") (pin "2") (pinfunction "2_2") (pintype "passive"))
    )
    (net (code "81") (name "XBEE14") (class "Default")
      (node (ref "H.X2") (pin "7") (pinfunction "7_7") (pintype "passive"))
      (node (ref "XBEE") (pin "14") (pinfunction "VREF_14") (pintype "input"))
    )
    (net (code "82") (name "XBEE15") (class "Default")
      (node (ref "H.X2") (pin "6") (pinfunction "6_6") (pintype "passive"))
      (node (ref "R7") (pin "1") (pinfunction "1_1") (pintype "bidirectional"))
      (node (ref "XBEE") (pin "15") (pinfunction "ASSOC/AD5/DIO5_15") (pintype "bidirectional"))
    )
    (net (code "83") (name "XBEE16") (class "Default")
      (node (ref "H.X2") (pin "5") (pinfunction "5_5") (pintype "passive"))
      (node (ref "XBEE") (pin "16") (pinfunction "~{RTS}/AD6/DIO6_16") (pintype "bidirectional"))
    )
    (net (code "84") (name "XBEE17") (class "Default")
      (node (ref "H.X2") (pin "4") (pinfunction "4_4") (pintype "passive"))
      (node (ref "XBEE") (pin "17") (pinfunction "COORD_SEL/AD3/DIO3_17") (pintype "bidirectional"))
    )
    (net (code "85") (name "XBEE18") (class "Default")
      (node (ref "H.X2") (pin "3") (pinfunction "3_3") (pintype "passive"))
      (node (ref "XBEE") (pin "18") (pinfunction "AD2/DIO2_18") (pintype "bidirectional"))
    )
    (net (code "86") (name "XBEE19") (class "Default")
      (node (ref "H.X2") (pin "2") (pinfunction "2_2") (pintype "passive"))
      (node (ref "XBEE") (pin "19") (pinfunction "AD1/DIO1_19") (pintype "bidirectional"))
    )
    (net (code "87") (name "XBEE20") (class "Default")
      (node (ref "CSND5") (pin "2") (pinfunction "2_2") (pintype "passive"))
      (node (ref "EXTERN") (pin "3") (pinfunction "3_3") (pintype "passive"))
      (node (ref "H.X2") (pin "1") (pinfunction "1_1") (pintype "passive"))
      (node (ref "XBEE") (pin "20") (pinfunction "AD0/DIO0_20") (pintype "bidirectional"))
      (node (ref "XCMSN") (pin "2") (pinfunction "2_2") (pintype "bidirectional"))
      (node (ref "XCMSN1") (pin "1") (pinfunction "1_1") (pintype "passive"))
    )
    (net (code "88") (name "unconnected-(5V-PadD+)") (class "Default")
      (node (ref "5V") (pin "D+") (pinfunction "D+_D+") (pintype "bidirectional"))
    )
    (net (code "89") (name "unconnected-(5V-PadD-)") (class "Default")
      (node (ref "5V") (pin "D-") (pinfunction "D-_D-") (pintype "bidirectional"))
    )
    (net (code "90") (name "unconnected-(5V-USBID-PadID)") (class "Default")
      (node (ref "5V") (pin "ID") (pinfunction "USBID_ID") (pintype "bidirectional"))
    )
    (net (code "91") (name "unconnected-(ARD.RST-Pad2)") (class "Default")
      (node (ref "ARD.RST") (pin "2") (pinfunction "2_2") (pintype "bidirectional"))
    )
    (net (code "92") (name "unconnected-(ARD.RST-Pad3)") (class "Default")
      (node (ref "ARD.RST") (pin "3") (pinfunction "3_3") (pintype "bidirectional"))
    )
    (net (code "93") (name "unconnected-(FTDI-CTS-Pad5)") (class "Default")
      (node (ref "FTDI") (pin "5") (pinfunction "CTS_5") (pintype "passive"))
    )
    (net (code "94") (name "unconnected-(PWR.EN-Pad1)") (class "Default")
      (node (ref "PWR.EN") (pin "1") (pinfunction "1_1") (pintype "bidirectional"))
    )
    (net (code "95") (name "unconnected-(PWR.EN-Pad2)") (class "Default")
      (node (ref "PWR.EN") (pin "2") (pinfunction "2_2") (pintype "bidirectional"))
    )
    (net (code "96") (name "unconnected-(PWR.EN-Pad3)") (class "Default")
      (node (ref "PWR.EN") (pin "3") (pinfunction "3_3") (pintype "bidirectional"))
    )
    (net (code "97") (name "unconnected-(PWR.EN-Pad6)") (class "Default")
      (node (ref "PWR.EN") (pin "6") (pinfunction "6_6") (pintype "bidirectional"))
    )
    (net (code "98") (name "unconnected-(U$9-DNC1-Pad1)") (class "Default")
      (node (ref "U$9") (pin "1") (pinfunction "DNC1_1") (pintype "bidirectional"))
    )
    (net (code "99") (name "unconnected-(U$9-DNC5-Pad5)") (class "Default")
      (node (ref "U$9") (pin "5") (pinfunction "DNC5_5") (pintype "bidirectional"))
    )
    (net (code "100") (name "unconnected-(U$9-DNC6-Pad6)") (class "Default")
      (node (ref "U$9") (pin "6") (pinfunction "DNC6_6") (pintype "bidirectional"))
    )
    (net (code "101") (name "unconnected-(U$9-DNC7-Pad7)") (class "Default")
      (node (ref "U$9") (pin "7") (pinfunction "DNC7_7") (pintype "bidirectional"))
    )
    (net (code "102") (name "unconnected-(U$9-DNC8-Pad8)") (class "Default")
      (node (ref "U$9") (pin "8") (pinfunction "DNC8_8") (pintype "bidirectional"))
    )
    (net (code "103") (name "unconnected-(XCMSN-Pad1)") (class "Default")
      (node (ref "XCMSN") (pin "1") (pinfunction "1_1") (pintype "bidirectional"))
    )
    (net (code "104") (name "unconnected-(XCMSN-Pad4)") (class "Default")
      (node (ref "XCMSN") (pin "4") (pinfunction "4_4") (pintype "bidirectional"))
    )
  )
)
